# ADCMP607-step-gen-BNC.net
KiCad netlist of a schematic drawn in EAGLE
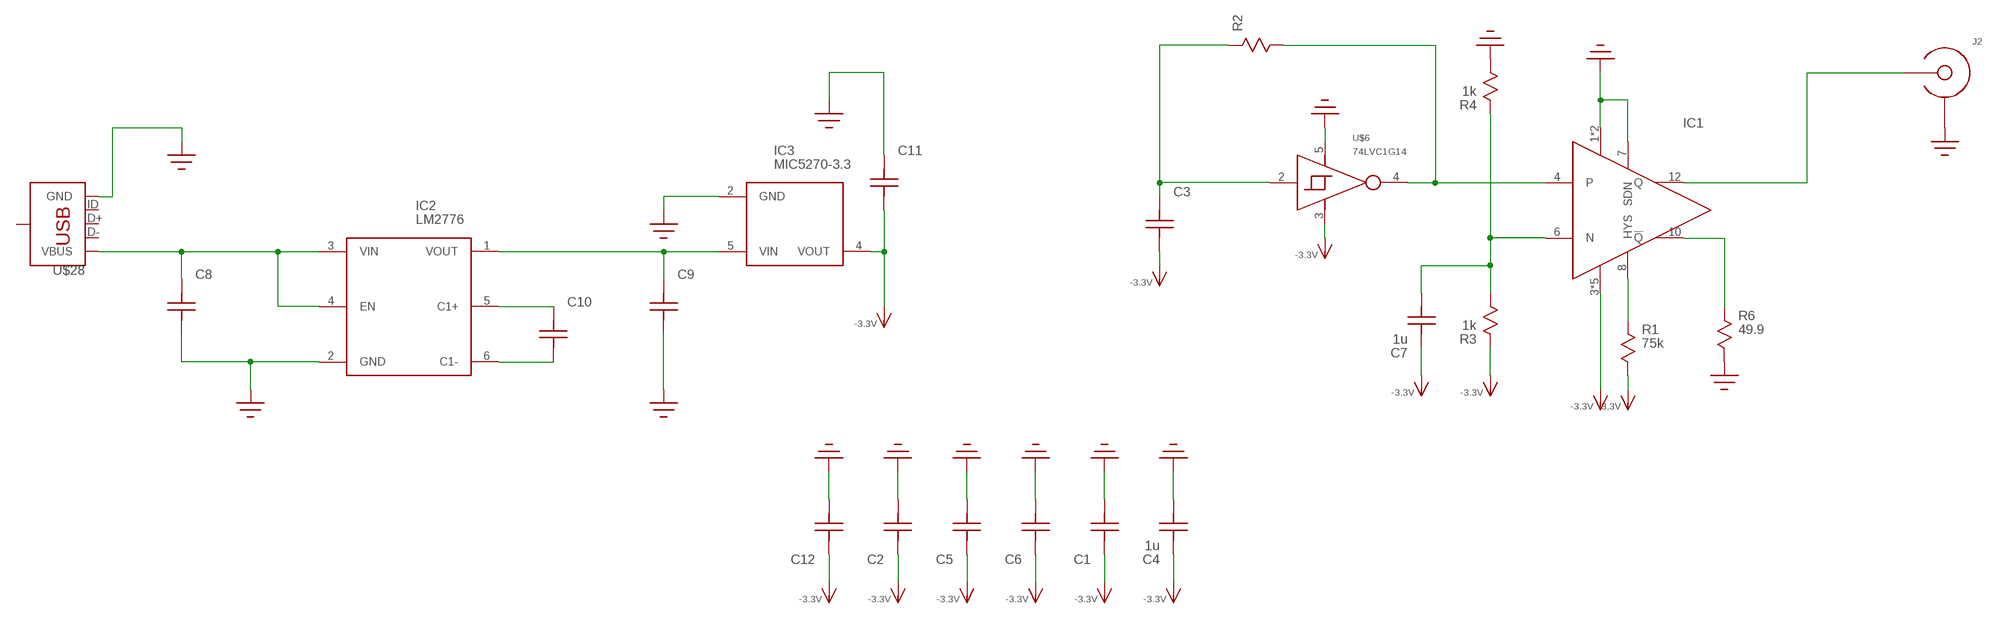
[diagram p0: schematic, sheet 1]

(export (version "E")
  (design (tool "Eeschema 10.0.6"))
  (components
    (comp (ref "C1")
      (value "C0603")
      (footprint "eagle-import:C0603")
      (libsource (lib "eagle-import") (part "C0603"))
    )
    (comp (ref "C2")
      (value "C0603")
      (footprint "eagle-import:C0603")
      (libsource (lib "eagle-import") (part "C0603"))
    )
    (comp (ref "C3")
      (value "C0603")
      (footprint "eagle-import:C0603")
      (libsource (lib "eagle-import") (part "C0603"))
    )
    (comp (ref "C4")
      (value "1u")
      (footprint "eagle-import:C0603")
      (libsource (lib "eagle-import") (part "C0603"))
    )
    (comp (ref "C5")
      (value "C0603")
      (footprint "eagle-import:C0603")
      (libsource (lib "eagle-import") (part "C0603"))
    )
    (comp (ref "C6")
      (value "C0603")
      (footprint "eagle-import:C0603")
      (libsource (lib "eagle-import") (part "C0603"))
    )
    (comp (ref "C7")
      (value "1u")
      (footprint "eagle-import:C0603")
      (libsource (lib "eagle-import") (part "C0603"))
    )
    (comp (ref "C8")
      (value "C1206")
      (footprint "eagle-import:1206")
      (libsource (lib "eagle-import") (part "C1206"))
    )
    (comp (ref "C9")
      (value "C1206")
      (footprint "eagle-import:1206")
      (libsource (lib "eagle-import") (part "C1206"))
    )
    (comp (ref "C10")
      (value "C0603")
      (footprint "eagle-import:C0603")
      (libsource (lib "eagle-import") (part "C0603"))
    )
    (comp (ref "C11")
      (value "C1206")
      (footprint "eagle-import:1206")
      (libsource (lib "eagle-import") (part "C1206"))
    )
    (comp (ref "C12")
      (value "C0603")
      (footprint "eagle-import:C0603")
      (libsource (lib "eagle-import") (part "C0603"))
    )
    (comp (ref "IC1")
      (value "ADCMP607")
      (footprint "eagle-import:QFN12-3X3")
      (libsource (lib "eagle-import") (part "ADCMP607"))
    )
    (comp (ref "IC2")
      (value "LM2776")
      (footprint "eagle-import:SOT23-6")
      (libsource (lib "eagle-import") (part "LM2776"))
    )
    (comp (ref "IC3")
      (value "MIC5270-3.3")
      (footprint "eagle-import:SOT23-5")
      (libsource (lib "eagle-import") (part "MIC5270"))
    )
    (comp (ref "J2")
      (value "BNC_MALE_PCB")
      (footprint "eagle-import:BNC_MALE_PCB")
      (libsource (lib "eagle-import") (part "BNC_MALE_PCB"))
    )
    (comp (ref "R1")
      (value "75k")
      (footprint "eagle-import:R0603")
      (libsource (lib "eagle-import") (part "R0603"))
    )
    (comp (ref "R2")
      (value "R0603")
      (footprint "eagle-import:R0603")
      (libsource (lib "eagle-import") (part "R0603"))
    )
    (comp (ref "R3")
      (value "1k")
      (footprint "eagle-import:R0603")
      (libsource (lib "eagle-import") (part "R0603"))
    )
    (comp (ref "R4")
      (value "1k")
      (footprint "eagle-import:R0603")
      (libsource (lib "eagle-import") (part "R0603"))
    )
    (comp (ref "R6")
      (value "49.9")
      (footprint "eagle-import:R0603")
      (libsource (lib "eagle-import") (part "R0603"))
    )
    (comp (ref "U$6")
      (value "74LVC1G14")
      (footprint "eagle-import:SOT23-5")
      (libsource (lib "eagle-import") (part "74LVC1G14"))
    )
    (comp (ref "U$28")
      (value "USB_MICRO_LEGS")
      (footprint "eagle-import:USB_MICRO_LEGS_2")
      (libsource (lib "eagle-import") (part "USB_MICRO_LEGS"))
    )
  )
  (nets
    (net (code "1") (name "-3.3V") (class "Default")
      (node (ref "C1") (pin "P$2") (pinfunction "P$2_P$2") (pintype "bidirectional"))
      (node (ref "C11") (pin "P$1") (pinfunction "P$1_P$1") (pintype "bidirectional"))
      (node (ref "C12") (pin "P$2") (pinfunction "P$2_P$2") (pintype "bidirectional"))
      (node (ref "C2") (pin "P$2") (pinfunction "P$2_P$2") (pintype "bidirectional"))
      (node (ref "C3") (pin "P$1") (pinfunction "P$1_P$1") (pintype "bidirectional"))
      (node (ref "C4") (pin "P$2") (pinfunction "P$2_P$2") (pintype "bidirectional"))
      (node (ref "C5") (pin "P$2") (pinfunction "P$2_P$2") (pintype "bidirectional"))
      (node (ref "C6") (pin "P$2") (pinfunction "P$2_P$2") (pintype "bidirectional"))
      (node (ref "C7") (pin "P$2") (pinfunction "P$2_P$2") (pintype "bidirectional"))
      (node (ref "IC1") (pin "11") (pinfunction "VEE_11") (pintype "bidirectional"))
      (node (ref "IC1") (pin "3") (pinfunction "VEE_3") (pintype "bidirectional"))
      (node (ref "IC1") (pin "5") (pinfunction "VEE_5") (pintype "bidirectional"))
      (node (ref "IC1") (pin "9") (pinfunction "VEE_9") (pintype "bidirectional"))
      (node (ref "IC1") (pin "EP") (pinfunction "VEE_EP") (pintype "bidirectional"))
      (node (ref "IC3") (pin "4") (pinfunction "VOUT_4") (pintype "bidirectional"))
      (node (ref "R1") (pin "P$2") (pinfunction "P$4_P$2") (pintype "bidirectional"))
      (node (ref "R3") (pin "P$1") (pinfunction "P$3_P$1") (pintype "bidirectional"))
      (node (ref "U$6") (pin "3") (pinfunction "GND_3") (pintype "bidirectional"))
    )
    (net (code "2") (name "GND") (class "Default")
      (node (ref "C1") (pin "P$1") (pinfunction "P$1_P$1") (pintype "bidirectional"))
      (node (ref "C11") (pin "P$2") (pinfunction "P$2_P$2") (pintype "bidirectional"))
      (node (ref "C12") (pin "P$1") (pinfunction "P$1_P$1") (pintype "bidirectional"))
      (node (ref "C2") (pin "P$1") (pinfunction "P$1_P$1") (pintype "bidirectional"))
      (node (ref "C4") (pin "P$1") (pinfunction "P$1_P$1") (pintype "bidirectional"))
      (node (ref "C5") (pin "P$1") (pinfunction "P$1_P$1") (pintype "bidirectional"))
      (node (ref "C6") (pin "P$1") (pinfunction "P$1_P$1") (pintype "bidirectional"))
      (node (ref "C8") (pin "P$1") (pinfunction "P$1_P$1") (pintype "bidirectional"))
      (node (ref "C9") (pin "P$1") (pinfunction "P$1_P$1") (pintype "bidirectional"))
      (node (ref "IC1") (pin "1") (pinfunction "VCC_1") (pintype "bidirectional"))
      (node (ref "IC1") (pin "2") (pinfunction "VCC_2") (pintype "bidirectional"))
      (node (ref "IC1") (pin "7") (pinfunction "SDN_7") (pintype "bidirectional"))
      (node (ref "IC2") (pin "2") (pinfunction "GND_2") (pintype "bidirectional"))
      (node (ref "IC3") (pin "2") (pinfunction "GND_2") (pintype "bidirectional"))
      (node (ref "J2") (pin "SHIELD@1") (pinfunction "SHIELD_SHIELD@1") (pintype "bidirectional"))
      (node (ref "J2") (pin "SHIELD@2") (pinfunction "SHIELD_SHIELD@2") (pintype "bidirectional"))
      (node (ref "J2") (pin "SHIELD@3") (pinfunction "SHIELD_SHIELD@3") (pintype "bidirectional"))
      (node (ref "J2") (pin "SHIELD@4") (pinfunction "SHIELD_SHIELD@4") (pintype "bidirectional"))
      (node (ref "R4") (pin "P$2") (pinfunction "P$4_P$2") (pintype "bidirectional"))
      (node (ref "R6") (pin "P$2") (pinfunction "P$4_P$2") (pintype "bidirectional"))
      (node (ref "U$28") (pin "GND") (pinfunction "GND_GND") (pintype "power_in"))
      (node (ref "U$6") (pin "5") (pinfunction "VCC_5") (pintype "bidirectional"))
    )
    (net (code "3") (name "Net-(IC1-HYS)") (class "Default")
      (node (ref "IC1") (pin "8") (pinfunction "HYS_8") (pintype "bidirectional"))
      (node (ref "R1") (pin "P$1") (pinfunction "P$3_P$1") (pintype "bidirectional"))
    )
    (net (code "4") (name "Net-(IC1-N)") (class "Default")
      (node (ref "C7") (pin "P$1") (pinfunction "P$1_P$1") (pintype "bidirectional"))
      (node (ref "IC1") (pin "6") (pinfunction "N_6") (pintype "bidirectional"))
      (node (ref "R3") (pin "P$2") (pinfunction "P$4_P$2") (pintype "bidirectional"))
      (node (ref "R4") (pin "P$1") (pinfunction "P$3_P$1") (pintype "bidirectional"))
    )
    (net (code "5") (name "Net-(IC1-P)") (class "Default")
      (node (ref "IC1") (pin "4") (pinfunction "P_4") (pintype "bidirectional"))
      (node (ref "R2") (pin "P$2") (pinfunction "P$4_P$2") (pintype "bidirectional"))
      (node (ref "U$6") (pin "4") (pinfunction "OUT_4") (pintype "bidirectional"))
    )
    (net (code "6") (name "Net-(IC1-Q)") (class "Default")
      (node (ref "IC1") (pin "12") (pinfunction "Q_12") (pintype "bidirectional"))
      (node (ref "J2") (pin "CENTER") (pinfunction "CENTER_CENTER") (pintype "bidirectional"))
    )
    (net (code "7") (name "Net-(IC1-~{Q})") (class "Default")
      (node (ref "IC1") (pin "10") (pinfunction "~{Q}_10") (pintype "bidirectional"))
      (node (ref "R6") (pin "P$1") (pinfunction "P$3_P$1") (pintype "bidirectional"))
    )
    (net (code "8") (name "Net-(IC2-C1+)") (class "Default")
      (node (ref "C10") (pin "P$2") (pinfunction "P$2_P$2") (pintype "bidirectional"))
      (node (ref "IC2") (pin "5") (pinfunction "C1+_5") (pintype "bidirectional"))
    )
    (net (code "9") (name "Net-(IC2-C1-)") (class "Default")
      (node (ref "C10") (pin "P$1") (pinfunction "P$1_P$1") (pintype "bidirectional"))
      (node (ref "IC2") (pin "6") (pinfunction "C1-_6") (pintype "bidirectional"))
    )
    (net (code "10") (name "Net-(IC2-EN)") (class "Default")
      (node (ref "C8") (pin "P$2") (pinfunction "P$2_P$2") (pintype "bidirectional"))
      (node (ref "IC2") (pin "3") (pinfunction "VIN_3") (pintype "bidirectional"))
      (node (ref "IC2") (pin "4") (pinfunction "EN_4") (pintype "bidirectional"))
      (node (ref "U$28") (pin "VBUS") (pinfunction "VBUS_VBUS") (pintype "power_in"))
    )
    (net (code "11") (name "Net-(IC2-VOUT)") (class "Default")
      (node (ref "C9") (pin "P$2") (pinfunction "P$2_P$2") (pintype "bidirectional"))
      (node (ref "IC2") (pin "1") (pinfunction "VOUT_1") (pintype "bidirectional"))
      (node (ref "IC3") (pin "5") (pinfunction "VIN_5") (pintype "bidirectional"))
    )
    (net (code "12") (name "Net-(R2-P$3)") (class "Default")
      (node (ref "C3") (pin "P$2") (pinfunction "P$2_P$2") (pintype "bidirectional"))
      (node (ref "R2") (pin "P$1") (pinfunction "P$3_P$1") (pintype "bidirectional"))
      (node (ref "U$6") (pin "2") (pinfunction "IN_2") (pintype "bidirectional"))
    )
    (net (code "13") (name "unconnected-(U$28-PadD+)") (class "Default")
      (node (ref "U$28") (pin "D+") (pinfunction "D+_D+") (pintype "bidirectional"))
    )
    (net (code "14") (name "unconnected-(U$28-PadD-)") (class "Default")
      (node (ref "U$28") (pin "D-") (pinfunction "D-_D-") (pintype "bidirectional"))
    )
    (net (code "15") (name "unconnected-(U$28-PadID)") (class "Default")
      (node (ref "U$28") (pin "ID") (pinfunction "ID_ID") (pintype "bidirectional"))
    )
    (net (code "16") (name "unconnected-(U$28-SHIELD-PadP$4)") (class "Default")
      (node (ref "U$28") (pin "P$4") (pinfunction "SHIELD_P$4") (pintype "bidirectional"))
    )
  )
)
